# Breakout.net
KiCad netlist of a schematic drawn in Altium Designer
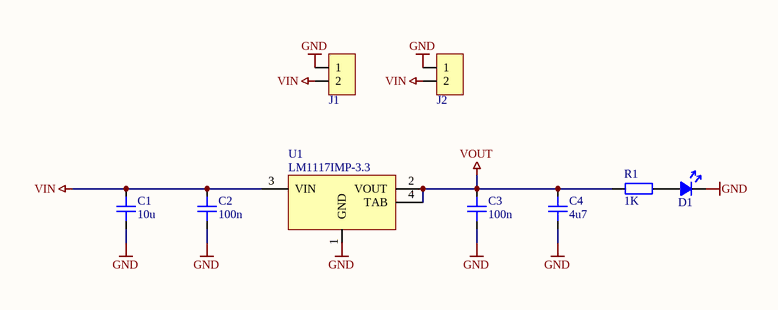
[diagram p0: Breakout.SchDoc]

(export (version "E")
  (design (tool "Eeschema 10.0.6"))
  (components
    (comp (ref "C1")
      (value "10u")
      (footprint "0805C_RF_M")
      (description "Capacitor")
      (fields (field (name "TOLERANCE") "?") (field (name "MANUFACTURER") "Generic Brand"))
      (libsource (lib "AG.Generic") (part "C"))
    )
    (comp (ref "C2")
      (value "100n")
      (footprint "0805C_RF_M")
      (description "Capacitor")
      (fields (field (name "TOLERANCE") "?") (field (name "MANUFACTURER") "Generic Brand"))
      (libsource (lib "AG.Generic") (part "C"))
    )
    (comp (ref "C3")
      (value "100n")
      (footprint "0805C_RF_M")
      (description "Capacitor")
      (fields (field (name "TOLERANCE") "?") (field (name "MANUFACTURER") "Generic Brand"))
      (libsource (lib "AG.Generic") (part "C"))
    )
    (comp (ref "C4")
      (value "4u7")
      (footprint "0805C_RF_M")
      (description "Capacitor")
      (fields (field (name "TOLERANCE") "?") (field (name "MANUFACTURER") "Generic Brand"))
      (libsource (lib "AG.Generic") (part "C"))
    )
    (comp (ref "D1")
      (value "Unspecified")
      (footprint "0805LED_RF_M")
      (description "LED")
      (fields (field (name "MANUFACTURER") "Generic Brand"))
      (libsource (lib "AG.Generic") (part "LED"))
    )
    (comp (ref "J1")
      (value "PINHDR-2P1")
      (footprint "HEADER-2.54-2P1")
      (description "Pin Header Single Row 2 Positions")
      (libsource (lib "AG.Connectors") (part "PINHDR-2P1"))
    )
    (comp (ref "J2")
      (value "PINHDR-2P1")
      (footprint "HEADER-2.54-2P1")
      (description "Pin Header Single Row 2 Positions")
      (libsource (lib "AG.Connectors") (part "PINHDR-2P1"))
    )
    (comp (ref "R1")
      (value "1K")
      (footprint "0805R_RF_M")
      (description "Resistor")
      (fields (field (name "TOLERANCE") "?") (field (name "MANUFACTURER") "Generic Brand"))
      (libsource (lib "AG.Generic") (part "R"))
    )
    (comp (ref "U1")
      (value "LM1117IMP-3.3")
      (footprint "SOT-223")
      (description "Voltage Regulator Linear 1% 800mA SOT-223")
      (fields (field (name "MANUFACTURER") "Texas Instruments"))
      (libsource (lib "AG.IC") (part "LM1117"))
    )
  )
  (nets
    (net (code "1") (name "GND") (class "Default")
      (node (ref "C1") (pin "1") (pinfunction "1_1") (pintype "passive"))
      (node (ref "C2") (pin "1") (pinfunction "1_1") (pintype "passive"))
      (node (ref "C3") (pin "1") (pinfunction "1_1") (pintype "passive"))
      (node (ref "C4") (pin "1") (pinfunction "1_1") (pintype "passive"))
      (node (ref "D1") (pin "C") (pinfunction "C_C") (pintype "passive"))
      (node (ref "J1") (pin "1") (pinfunction "1_1") (pintype "passive"))
      (node (ref "J2") (pin "1") (pinfunction "1_1") (pintype "passive"))
      (node (ref "U1") (pin "1") (pinfunction "GND_1") (pintype "passive"))
    )
    (net (code "2") (name "Net-(D1-PadA)") (class "Default")
      (node (ref "D1") (pin "A") (pinfunction "A_A") (pintype "passive"))
      (node (ref "R1") (pin "2") (pintype "passive"))
    )
    (net (code "3") (name "VIN") (class "Default")
      (node (ref "C1") (pin "2") (pinfunction "2_2") (pintype "passive"))
      (node (ref "C2") (pin "2") (pinfunction "2_2") (pintype "passive"))
      (node (ref "J1") (pin "2") (pinfunction "2_2") (pintype "passive"))
      (node (ref "J2") (pin "2") (pinfunction "2_2") (pintype "passive"))
      (node (ref "U1") (pin "3") (pinfunction "VIN_3") (pintype "passive"))
    )
    (net (code "4") (name "VOUT") (class "Default")
      (node (ref "C3") (pin "2") (pinfunction "2_2") (pintype "passive"))
      (node (ref "C4") (pin "2") (pinfunction "2_2") (pintype "passive"))
      (node (ref "R1") (pin "1") (pintype "passive"))
      (node (ref "U1") (pin "2") (pinfunction "VOUT_2") (pintype "passive"))
      (node (ref "U1") (pin "4") (pinfunction "TAB_4") (pintype "passive"))
    )
  )
)
